# sensor_board_6_1_0.net
KiCad netlist of a schematic drawn in EAGLE
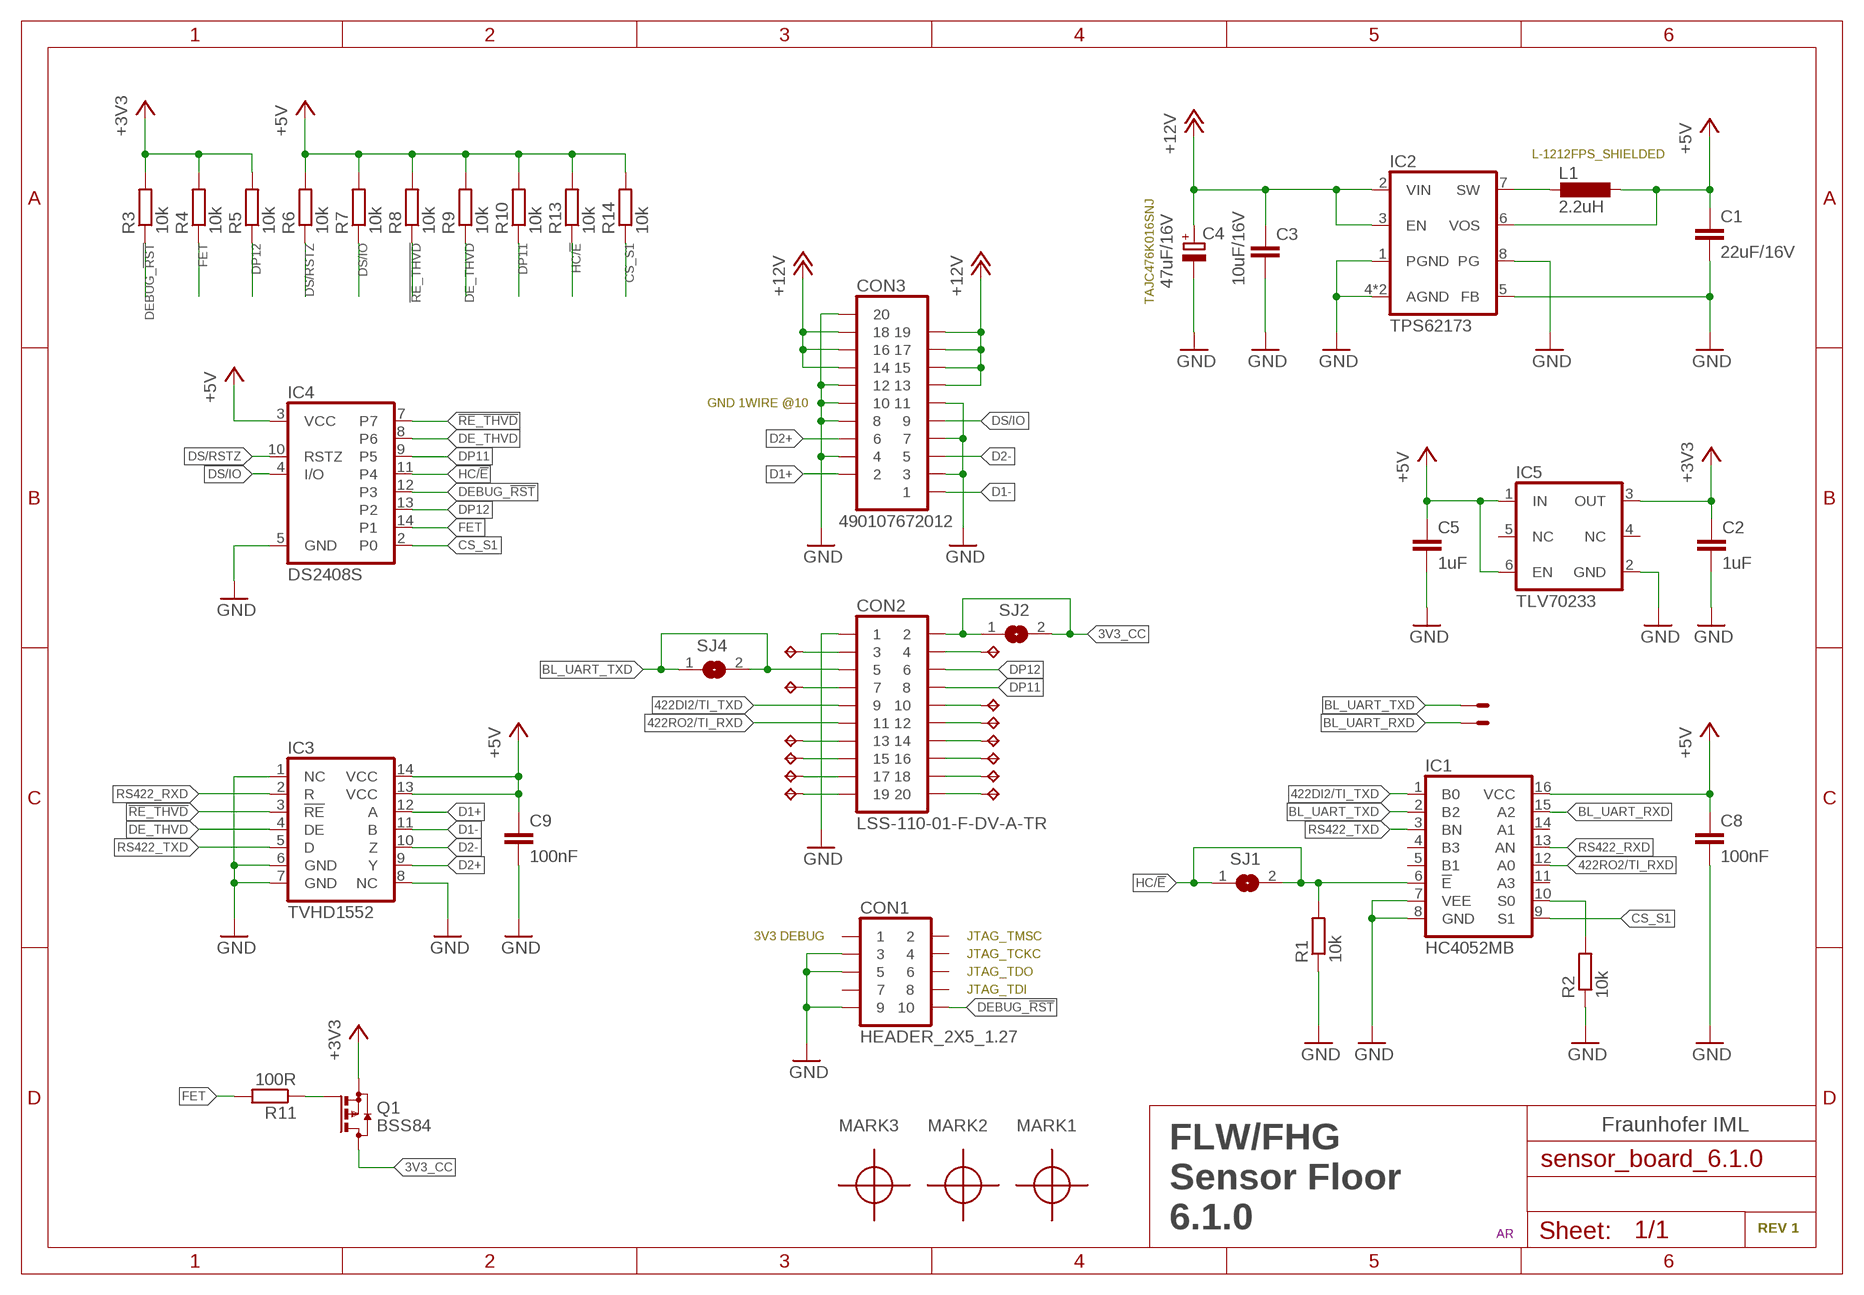
[diagram p0: schematic, sheet 1]

(export (version "E")
  (design (tool "Eeschema 10.0.6"))
  (components
    (comp (ref "C1")
      (value "22uF/16V")
      (footprint "eagle-import:C0805K")
      (libsource (lib "eagle-import") (part "C-EUC0805K"))
    )
    (comp (ref "C2")
      (value "1uF")
      (footprint "eagle-import:C0603")
      (libsource (lib "eagle-import") (part "C0603"))
    )
    (comp (ref "C3")
      (value "10uF/16V")
      (footprint "eagle-import:C0805K")
      (libsource (lib "eagle-import") (part "C-EUC0805K"))
    )
    (comp (ref "C4")
      (value "47uF/16V")
      (footprint "eagle-import:C_6032-28R")
      (libsource (lib "eagle-import") (part "CPOL-EUC/6032-28R"))
    )
    (comp (ref "C5")
      (value "1uF")
      (footprint "eagle-import:C0603")
      (libsource (lib "eagle-import") (part "C0603"))
    )
    (comp (ref "C8")
      (value "100nF")
      (footprint "eagle-import:C0402")
      (libsource (lib "eagle-import") (part "C0402"))
    )
    (comp (ref "C9")
      (value "100nF")
      (footprint "eagle-import:C0402")
      (libsource (lib "eagle-import") (part "C0402"))
    )
    (comp (ref "CON1")
      (value "HEADER_2X5_1.27")
      (footprint "eagle-import:HEADER_2X5_1.27")
      (libsource (lib "eagle-import") (part "HEADER_2X5_1.27"))
    )
    (comp (ref "CON2")
      (value "LSS-110-01-F-DV-A-TR")
      (footprint "eagle-import:LSS-110-01-F-DV-A-TR")
      (libsource (lib "eagle-import") (part "LSS-110-01-F-DV-A-TR"))
    )
    (comp (ref "CON3")
      (value "490107672012")
      (footprint "eagle-import:490107672012")
      (libsource (lib "eagle-import") (part "490107672012"))
    )
    (comp (ref "IC1")
      (value "HC4052MB")
      (footprint "eagle-import:SO16")
      (libsource (lib "eagle-import") (part "HC4052MB"))
    )
    (comp (ref "IC2")
      (value "TPS62173")
      (footprint "eagle-import:WSON8")
      (libsource (lib "eagle-import") (part "TPS62173"))
    )
    (comp (ref "IC3")
      (value "TVHD1552")
      (footprint "eagle-import:SO14")
      (libsource (lib "eagle-import") (part "TVHD1552"))
    )
    (comp (ref "IC4")
      (value "DS2408S")
      (footprint "eagle-import:SO16")
      (libsource (lib "eagle-import") (part "DS2408S"))
    )
    (comp (ref "IC5")
      (value "TLV70233")
      (footprint "eagle-import:S-PDSO-N6")
      (libsource (lib "eagle-import") (part "TLV70233"))
    )
    (comp (ref "L1")
      (value "2.2uH")
      (footprint "eagle-import:L-1212FPS_SHIELDED")
      (libsource (lib "eagle-import") (part "L-1212FPS_SHIELDED"))
    )
    (comp (ref "MARK1")
      (value "PASSMARK")
      (footprint "eagle-import:PASSMARK")
      (libsource (lib "eagle-import") (part "PASSMARK"))
    )
    (comp (ref "MARK2")
      (value "PASSMARK")
      (footprint "eagle-import:PASSMARK")
      (libsource (lib "eagle-import") (part "PASSMARK"))
    )
    (comp (ref "MARK3")
      (value "PASSMARK")
      (footprint "eagle-import:PASSMARK")
      (libsource (lib "eagle-import") (part "PASSMARK"))
    )
    (comp (ref "Q1")
      (value "BSS84")
      (footprint "eagle-import:SOT23")
      (libsource (lib "eagle-import") (part "BSS84"))
    )
    (comp (ref "R1")
      (value "10k")
      (footprint "eagle-import:R0402")
      (libsource (lib "eagle-import") (part "R0402"))
    )
    (comp (ref "R2")
      (value "10k")
      (footprint "eagle-import:R0402")
      (libsource (lib "eagle-import") (part "R0402"))
    )
    (comp (ref "R3")
      (value "10k")
      (footprint "eagle-import:R0402")
      (libsource (lib "eagle-import") (part "R0402"))
    )
    (comp (ref "R4")
      (value "10k")
      (footprint "eagle-import:R0402")
      (libsource (lib "eagle-import") (part "R0402"))
    )
    (comp (ref "R5")
      (value "10k")
      (footprint "eagle-import:R0402")
      (libsource (lib "eagle-import") (part "R0402"))
    )
    (comp (ref "R6")
      (value "10k")
      (footprint "eagle-import:R0402")
      (libsource (lib "eagle-import") (part "R0402"))
    )
    (comp (ref "R7")
      (value "10k")
      (footprint "eagle-import:R0402")
      (libsource (lib "eagle-import") (part "R0402"))
    )
    (comp (ref "R8")
      (value "10k")
      (footprint "eagle-import:R0402")
      (libsource (lib "eagle-import") (part "R0402"))
    )
    (comp (ref "R9")
      (value "10k")
      (footprint "eagle-import:R0402")
      (libsource (lib "eagle-import") (part "R0402"))
    )
    (comp (ref "R10")
      (value "10k")
      (footprint "eagle-import:R0402")
      (libsource (lib "eagle-import") (part "R0402"))
    )
    (comp (ref "R11")
      (value "100R")
      (footprint "eagle-import:R0402")
      (libsource (lib "eagle-import") (part "R0402"))
    )
    (comp (ref "R13")
      (value "10k")
      (footprint "eagle-import:R0402")
      (libsource (lib "eagle-import") (part "R0402"))
    )
    (comp (ref "R14")
      (value "10k")
      (footprint "eagle-import:R0402")
      (libsource (lib "eagle-import") (part "R0402"))
    )
    (comp (ref "SJ1")
      (value "SJT")
      (footprint "eagle-import:SJT")
      (libsource (lib "eagle-import") (part "SJT"))
    )
    (comp (ref "SJ2")
      (value "SJT")
      (footprint "eagle-import:SJT")
      (libsource (lib "eagle-import") (part "SJT"))
    )
    (comp (ref "SJ4")
      (value "SJT")
      (footprint "eagle-import:SJT")
      (libsource (lib "eagle-import") (part "SJT"))
    )
    (comp (ref "TP1")
      (value "TP/SP-1.5X1.0")
      (footprint "eagle-import:SOLDERPAD_1.5X1.0")
      (libsource (lib "eagle-import") (part "TP/SP-1.5X1.0"))
    )
    (comp (ref "TP2")
      (value "TPTP08R")
      (footprint "eagle-import:TP08R")
      (libsource (lib "eagle-import") (part "TPTP08R"))
    )
    (comp (ref "TP3")
      (value "TPTP08R")
      (footprint "eagle-import:TP08R")
      (libsource (lib "eagle-import") (part "TPTP08R"))
    )
    (comp (ref "TP4")
      (value "TP/SP-1.5X1.0")
      (footprint "eagle-import:SOLDERPAD_1.5X1.0")
      (libsource (lib "eagle-import") (part "TP/SP-1.5X1.0"))
    )
    (comp (ref "TP5")
      (value "TPTP08R")
      (footprint "eagle-import:TP08R")
      (libsource (lib "eagle-import") (part "TPTP08R"))
    )
    (comp (ref "TP6")
      (value "TPTP08R")
      (footprint "eagle-import:TP08R")
      (libsource (lib "eagle-import") (part "TPTP08R"))
    )
    (comp (ref "TP7")
      (value "TPTP08R")
      (footprint "eagle-import:TP08R")
      (libsource (lib "eagle-import") (part "TPTP08R"))
    )
    (comp (ref "TP8")
      (value "TPTP08R")
      (footprint "eagle-import:TP08R")
      (libsource (lib "eagle-import") (part "TPTP08R"))
    )
    (comp (ref "TP9")
      (value "TPTP08R")
      (footprint "eagle-import:TP08R")
      (libsource (lib "eagle-import") (part "TPTP08R"))
    )
    (comp (ref "TP10")
      (value "TPTP08R")
      (footprint "eagle-import:TP08R")
      (libsource (lib "eagle-import") (part "TPTP08R"))
    )
    (comp (ref "TP11")
      (value "TPTP08R")
      (footprint "eagle-import:TP08R")
      (libsource (lib "eagle-import") (part "TPTP08R"))
    )
    (comp (ref "TP12")
      (value "TPTP08R")
      (footprint "eagle-import:TP08R")
      (libsource (lib "eagle-import") (part "TPTP08R"))
    )
    (comp (ref "TP13")
      (value "TPTP08R")
      (footprint "eagle-import:TP08R")
      (libsource (lib "eagle-import") (part "TPTP08R"))
    )
    (comp (ref "TP14")
      (value "TPTP08R")
      (footprint "eagle-import:TP08R")
      (libsource (lib "eagle-import") (part "TPTP08R"))
    )
    (comp (ref "TP15")
      (value "TPTP08R")
      (footprint "eagle-import:TP08R")
      (libsource (lib "eagle-import") (part "TPTP08R"))
    )
  )
  (nets
    (net (code "1") (name "+3V3") (class "Default")
      (node (ref "C2") (pin "1") (pinfunction "1_1") (pintype "passive"))
      (node (ref "IC5") (pin "3") (pinfunction "OUT_3") (pintype "power_in"))
      (node (ref "Q1") (pin "2") (pinfunction "S_2") (pintype "passive"))
      (node (ref "R3") (pin "P$2") (pinfunction "2_P$2") (pintype "passive"))
      (node (ref "R4") (pin "P$2") (pinfunction "2_P$2") (pintype "passive"))
      (node (ref "R5") (pin "P$2") (pinfunction "2_P$2") (pintype "passive"))
    )
    (net (code "2") (name "+5V") (class "Default")
      (node (ref "C1") (pin "1") (pinfunction "1_1") (pintype "passive"))
      (node (ref "C5") (pin "1") (pinfunction "1_1") (pintype "passive"))
      (node (ref "C8") (pin "P$1") (pinfunction "1_P$1") (pintype "passive"))
      (node (ref "C9") (pin "P$1") (pinfunction "1_P$1") (pintype "passive"))
      (node (ref "IC1") (pin "16") (pinfunction "VCC_16") (pintype "bidirectional"))
      (node (ref "IC2") (pin "6") (pinfunction "VOS_6") (pintype "bidirectional"))
      (node (ref "IC3") (pin "13") (pinfunction "VCC_13") (pintype "bidirectional"))
      (node (ref "IC3") (pin "14") (pinfunction "VCC_14") (pintype "bidirectional"))
      (node (ref "IC4") (pin "3") (pinfunction "VCC_3") (pintype "power_in"))
      (node (ref "IC5") (pin "1") (pinfunction "IN_1") (pintype "power_in"))
      (node (ref "IC5") (pin "6") (pinfunction "EN_6") (pintype "input"))
      (node (ref "L1") (pin "1") (pinfunction "1_1") (pintype "passive"))
      (node (ref "R10") (pin "P$2") (pinfunction "2_P$2") (pintype "passive"))
      (node (ref "R13") (pin "P$2") (pinfunction "2_P$2") (pintype "passive"))
      (node (ref "R14") (pin "P$2") (pinfunction "2_P$2") (pintype "passive"))
      (node (ref "R6") (pin "P$2") (pinfunction "2_P$2") (pintype "passive"))
      (node (ref "R7") (pin "P$2") (pinfunction "2_P$2") (pintype "passive"))
      (node (ref "R8") (pin "P$2") (pinfunction "2_P$2") (pintype "passive"))
      (node (ref "R9") (pin "P$2") (pinfunction "2_P$2") (pintype "passive"))
    )
    (net (code "3") (name "+12V") (class "Default")
      (node (ref "C3") (pin "1") (pinfunction "1_1") (pintype "passive"))
      (node (ref "C4") (pin "+") (pinfunction "+_+") (pintype "passive"))
      (node (ref "CON3") (pin "13") (pinfunction "13_13") (pintype "passive"))
      (node (ref "CON3") (pin "14") (pinfunction "14_14") (pintype "passive"))
      (node (ref "CON3") (pin "15") (pinfunction "15_15") (pintype "passive"))
      (node (ref "CON3") (pin "16") (pinfunction "16_16") (pintype "passive"))
      (node (ref "CON3") (pin "17") (pinfunction "17_17") (pintype "passive"))
      (node (ref "CON3") (pin "18") (pinfunction "18_18") (pintype "passive"))
      (node (ref "CON3") (pin "19") (pinfunction "19_19") (pintype "passive"))
      (node (ref "IC2") (pin "2") (pinfunction "VIN_2") (pintype "bidirectional"))
      (node (ref "IC2") (pin "3") (pinfunction "EN_3") (pintype "bidirectional"))
    )
    (net (code "4") (name "/DEBUG_~{RST}") (class "Default")
      (node (ref "CON1") (pin "P$10") (pinfunction "10_P$10") (pintype "bidirectional"))
      (node (ref "IC4") (pin "12") (pinfunction "P3_12") (pintype "open_collector"))
      (node (ref "R3") (pin "P$1") (pinfunction "1_P$1") (pintype "passive"))
    )
    (net (code "5") (name "/HC{slash}~{E}") (class "Default")
      (node (ref "IC1") (pin "6") (pinfunction "~{E}_6") (pintype "bidirectional"))
      (node (ref "IC4") (pin "11") (pinfunction "P4_11") (pintype "open_collector"))
      (node (ref "R1") (pin "P$2") (pinfunction "2_P$2") (pintype "passive"))
      (node (ref "R13") (pin "P$1") (pinfunction "1_P$1") (pintype "passive"))
      (node (ref "SJ1") (pin "1") (pinfunction "1_1") (pintype "passive"))
      (node (ref "SJ1") (pin "2") (pinfunction "2_2") (pintype "passive"))
    )
    (net (code "6") (name "/~{RE_THVD}") (class "Default")
      (node (ref "IC3") (pin "3") (pinfunction "~{RE}_3") (pintype "bidirectional"))
      (node (ref "IC4") (pin "7") (pinfunction "P7_7") (pintype "open_collector"))
      (node (ref "R8") (pin "P$1") (pinfunction "1_P$1") (pintype "passive"))
    )
    (net (code "7") (name "3V3_CC") (class "Default")
      (node (ref "CON2") (pin "P2") (pinfunction "2_P2") (pintype "bidirectional"))
      (node (ref "Q1") (pin "3") (pinfunction "D_3") (pintype "passive"))
      (node (ref "SJ2") (pin "1") (pinfunction "1_1") (pintype "passive"))
      (node (ref "SJ2") (pin "2") (pinfunction "2_2") (pintype "passive"))
    )
    (net (code "8") (name "422DI2{slash}TI_TXD") (class "Default")
      (node (ref "CON2") (pin "P9") (pinfunction "9_P9") (pintype "bidirectional"))
      (node (ref "IC1") (pin "1") (pinfunction "B0_1") (pintype "bidirectional"))
    )
    (net (code "9") (name "422RO2{slash}TI_RXD") (class "Default")
      (node (ref "CON2") (pin "P11") (pinfunction "11_P11") (pintype "bidirectional"))
      (node (ref "IC1") (pin "12") (pinfunction "A0_12") (pintype "bidirectional"))
    )
    (net (code "10") (name "BL_UART_RXD") (class "Default")
      (node (ref "IC1") (pin "15") (pinfunction "A2_15") (pintype "bidirectional"))
      (node (ref "TP4") (pin "1") (pinfunction "S_1") (pintype "passive"))
    )
    (net (code "11") (name "BL_UART_TXD") (class "Default")
      (node (ref "CON2") (pin "P5") (pinfunction "5_P5") (pintype "bidirectional"))
      (node (ref "IC1") (pin "2") (pinfunction "B2_2") (pintype "bidirectional"))
      (node (ref "SJ4") (pin "1") (pinfunction "1_1") (pintype "passive"))
      (node (ref "SJ4") (pin "2") (pinfunction "2_2") (pintype "passive"))
      (node (ref "TP1") (pin "1") (pinfunction "S_1") (pintype "passive"))
    )
    (net (code "12") (name "CS_S1") (class "Default")
      (node (ref "IC1") (pin "9") (pinfunction "S1_9") (pintype "bidirectional"))
      (node (ref "IC4") (pin "2") (pinfunction "P0_2") (pintype "open_collector"))
      (node (ref "R14") (pin "P$1") (pinfunction "1_P$1") (pintype "passive"))
    )
    (net (code "13") (name "D1+") (class "Default")
      (node (ref "CON3") (pin "2") (pinfunction "2_2") (pintype "passive"))
      (node (ref "IC3") (pin "12") (pinfunction "A_12") (pintype "bidirectional"))
    )
    (net (code "14") (name "D1-") (class "Default")
      (node (ref "CON3") (pin "1") (pinfunction "1_1") (pintype "passive"))
      (node (ref "IC3") (pin "11") (pinfunction "B_11") (pintype "bidirectional"))
    )
    (net (code "15") (name "D2+") (class "Default")
      (node (ref "CON3") (pin "6") (pinfunction "6_6") (pintype "passive"))
      (node (ref "IC3") (pin "9") (pinfunction "Y_9") (pintype "bidirectional"))
    )
    (net (code "16") (name "D2-") (class "Default")
      (node (ref "CON3") (pin "5") (pinfunction "5_5") (pintype "passive"))
      (node (ref "IC3") (pin "10") (pinfunction "Z_10") (pintype "bidirectional"))
    )
    (net (code "17") (name "DE_THVD") (class "Default")
      (node (ref "IC3") (pin "4") (pinfunction "DE_4") (pintype "bidirectional"))
      (node (ref "IC4") (pin "8") (pinfunction "P6_8") (pintype "open_collector"))
      (node (ref "R9") (pin "P$1") (pinfunction "1_P$1") (pintype "passive"))
    )
    (net (code "18") (name "DP11") (class "Default")
      (node (ref "CON2") (pin "P8") (pinfunction "8_P8") (pintype "bidirectional"))
      (node (ref "IC4") (pin "9") (pinfunction "P5_9") (pintype "open_collector"))
      (node (ref "R10") (pin "P$1") (pinfunction "1_P$1") (pintype "passive"))
    )
    (net (code "19") (name "DP12") (class "Default")
      (node (ref "CON2") (pin "P6") (pinfunction "6_P6") (pintype "bidirectional"))
      (node (ref "IC4") (pin "13") (pinfunction "P2_13") (pintype "open_collector"))
      (node (ref "R5") (pin "P$1") (pinfunction "1_P$1") (pintype "passive"))
    )
    (net (code "20") (name "DS{slash}IO") (class "Default")
      (node (ref "CON3") (pin "9") (pinfunction "9_9") (pintype "passive"))
      (node (ref "IC4") (pin "4") (pinfunction "I/O_4") (pintype "open_collector"))
      (node (ref "R7") (pin "P$1") (pinfunction "1_P$1") (pintype "passive"))
    )
    (net (code "21") (name "DS{slash}RSTZ") (class "Default")
      (node (ref "IC4") (pin "10") (pinfunction "RSTZ_10") (pintype "open_collector"))
      (node (ref "R6") (pin "P$1") (pinfunction "1_P$1") (pintype "passive"))
    )
    (net (code "22") (name "FET") (class "Default")
      (node (ref "IC4") (pin "14") (pinfunction "P1_14") (pintype "open_collector"))
      (node (ref "R11") (pin "P$2") (pinfunction "2_P$2") (pintype "passive"))
      (node (ref "R4") (pin "P$1") (pinfunction "1_P$1") (pintype "passive"))
    )
    (net (code "23") (name "GND") (class "Default")
      (node (ref "C1") (pin "2") (pinfunction "2_2") (pintype "passive"))
      (node (ref "C2") (pin "2") (pinfunction "2_2") (pintype "passive"))
      (node (ref "C3") (pin "2") (pinfunction "2_2") (pintype "passive"))
      (node (ref "C4") (pin "-") (pinfunction "-_-") (pintype "passive"))
      (node (ref "C5") (pin "2") (pinfunction "2_2") (pintype "passive"))
      (node (ref "C8") (pin "P$2") (pinfunction "2_P$2") (pintype "passive"))
      (node (ref "C9") (pin "P$2") (pinfunction "2_P$2") (pintype "passive"))
      (node (ref "CON1") (pin "P$3") (pinfunction "3_P$3") (pintype "bidirectional"))
      (node (ref "CON1") (pin "P$5") (pinfunction "5_P$5") (pintype "bidirectional"))
      (node (ref "CON1") (pin "P$9") (pinfunction "9_P$9") (pintype "bidirectional"))
      (node (ref "CON2") (pin "P1") (pinfunction "1_P1") (pintype "bidirectional"))
      (node (ref "CON3") (pin "10") (pinfunction "10_10") (pintype "passive"))
      (node (ref "CON3") (pin "11") (pinfunction "11_11") (pintype "passive"))
      (node (ref "CON3") (pin "12") (pinfunction "12_12") (pintype "passive"))
      (node (ref "CON3") (pin "20") (pinfunction "20_20") (pintype "passive"))
      (node (ref "CON3") (pin "3") (pinfunction "3_3") (pintype "passive"))
      (node (ref "CON3") (pin "4") (pinfunction "4_4") (pintype "passive"))
      (node (ref "CON3") (pin "7") (pinfunction "7_7") (pintype "passive"))
      (node (ref "CON3") (pin "8") (pinfunction "8_8") (pintype "passive"))
      (node (ref "IC1") (pin "7") (pinfunction "VEE_7") (pintype "bidirectional"))
      (node (ref "IC1") (pin "8") (pinfunction "GND_8") (pintype "bidirectional"))
      (node (ref "IC2") (pin "1") (pinfunction "PGND_1") (pintype "bidirectional"))
      (node (ref "IC2") (pin "4") (pinfunction "AGND_4") (pintype "bidirectional"))
      (node (ref "IC2") (pin "5") (pinfunction "FB_5") (pintype "bidirectional"))
      (node (ref "IC2") (pin "8") (pinfunction "PG_8") (pintype "bidirectional"))
      (node (ref "IC2") (pin "EXP") (pinfunction "AGND_EXP") (pintype "bidirectional"))
      (node (ref "IC3") (pin "1") (pinfunction "NC_1") (pintype "bidirectional"))
      (node (ref "IC3") (pin "6") (pinfunction "GND_6") (pintype "bidirectional"))
      (node (ref "IC3") (pin "7") (pinfunction "GND_7") (pintype "bidirectional"))
      (node (ref "IC3") (pin "8") (pinfunction "NC_8") (pintype "bidirectional"))
      (node (ref "IC4") (pin "5") (pinfunction "GND_5") (pintype "power_in"))
      (node (ref "IC5") (pin "2") (pinfunction "GND_2") (pintype "power_in"))
      (node (ref "R1") (pin "P$1") (pinfunction "1_P$1") (pintype "passive"))
      (node (ref "R2") (pin "P$1") (pinfunction "1_P$1") (pintype "passive"))
    )
    (net (code "24") (name "Net-(CON2-3)") (class "Default")
      (node (ref "CON2") (pin "P3") (pinfunction "3_P3") (pintype "bidirectional"))
      (node (ref "TP15") (pin "TP") (pinfunction "TP_TP") (pintype "input"))
    )
    (net (code "25") (name "Net-(CON2-4)") (class "Default")
      (node (ref "CON2") (pin "P4") (pinfunction "4_P4") (pintype "bidirectional"))
      (node (ref "TP14") (pin "TP") (pinfunction "TP_TP") (pintype "input"))
    )
    (net (code "26") (name "Net-(CON2-7)") (class "Default")
      (node (ref "CON2") (pin "P7") (pinfunction "7_P7") (pintype "bidirectional"))
      (node (ref "TP13") (pin "TP") (pinfunction "TP_TP") (pintype "input"))
    )
    (net (code "27") (name "Net-(CON2-10)") (class "Default")
      (node (ref "CON2") (pin "P10") (pinfunction "10_P10") (pintype "bidirectional"))
      (node (ref "TP3") (pin "TP") (pinfunction "TP_TP") (pintype "input"))
    )
    (net (code "28") (name "Net-(CON2-12)") (class "Default")
      (node (ref "CON2") (pin "P12") (pinfunction "12_P12") (pintype "bidirectional"))
      (node (ref "TP2") (pin "TP") (pinfunction "TP_TP") (pintype "input"))
    )
    (net (code "29") (name "Net-(CON2-13)") (class "Default")
      (node (ref "CON2") (pin "P13") (pinfunction "13_P13") (pintype "bidirectional"))
      (node (ref "TP12") (pin "TP") (pinfunction "TP_TP") (pintype "input"))
    )
    (net (code "30") (name "Net-(CON2-14)") (class "Default")
      (node (ref "CON2") (pin "P14") (pinfunction "14_P14") (pintype "bidirectional"))
      (node (ref "TP5") (pin "TP") (pinfunction "TP_TP") (pintype "input"))
    )
    (net (code "31") (name "Net-(CON2-15)") (class "Default")
      (node (ref "CON2") (pin "P15") (pinfunction "15_P15") (pintype "bidirectional"))
      (node (ref "TP11") (pin "TP") (pinfunction "TP_TP") (pintype "input"))
    )
    (net (code "32") (name "Net-(CON2-16)") (class "Default")
      (node (ref "CON2") (pin "P16") (pinfunction "16_P16") (pintype "bidirectional"))
      (node (ref "TP6") (pin "TP") (pinfunction "TP_TP") (pintype "input"))
    )
    (net (code "33") (name "Net-(CON2-17)") (class "Default")
      (node (ref "CON2") (pin "P17") (pinfunction "17_P17") (pintype "bidirectional"))
      (node (ref "TP10") (pin "TP") (pinfunction "TP_TP") (pintype "input"))
    )
    (net (code "34") (name "Net-(CON2-18)") (class "Default")
      (node (ref "CON2") (pin "P18") (pinfunction "18_P18") (pintype "bidirectional"))
      (node (ref "TP7") (pin "TP") (pinfunction "TP_TP") (pintype "input"))
    )
    (net (code "35") (name "Net-(CON2-19)") (class "Default")
      (node (ref "CON2") (pin "P19") (pinfunction "19_P19") (pintype "bidirectional"))
      (node (ref "TP9") (pin "TP") (pinfunction "TP_TP") (pintype "input"))
    )
    (net (code "36") (name "Net-(CON2-20)") (class "Default")
      (node (ref "CON2") (pin "P20") (pinfunction "20_P20") (pintype "bidirectional"))
      (node (ref "TP8") (pin "TP") (pinfunction "TP_TP") (pintype "input"))
    )
    (net (code "37") (name "Net-(IC1-S0)") (class "Default")
      (node (ref "IC1") (pin "10") (pinfunction "S0_10") (pintype "bidirectional"))
      (node (ref "R2") (pin "P$2") (pinfunction "2_P$2") (pintype "passive"))
    )
    (net (code "38") (name "Net-(IC2-SW)") (class "Default")
      (node (ref "IC2") (pin "7") (pinfunction "SW_7") (pintype "bidirectional"))
      (node (ref "L1") (pin "2") (pinfunction "2_2") (pintype "passive"))
    )
    (net (code "39") (name "Net-(Q1-G)") (class "Default")
      (node (ref "Q1") (pin "1") (pinfunction "G_1") (pintype "passive"))
      (node (ref "R11") (pin "P$1") (pinfunction "1_P$1") (pintype "passive"))
    )
    (net (code "40") (name "RS422_RXD") (class "Default")
      (node (ref "IC1") (pin "13") (pinfunction "AN_13") (pintype "bidirectional"))
      (node (ref "IC3") (pin "2") (pinfunction "R_2") (pintype "bidirectional"))
    )
    (net (code "41") (name "RS422_TXD") (class "Default")
      (node (ref "IC1") (pin "3") (pinfunction "BN_3") (pintype "bidirectional"))
      (node (ref "IC3") (pin "5") (pinfunction "D_5") (pintype "bidirectional"))
    )
    (net (code "42") (name "unconnected-(CON1-1-PadP$1)") (class "Default")
      (node (ref "CON1") (pin "P$1") (pinfunction "1_P$1") (pintype "bidirectional"))
    )
    (net (code "43") (name "unconnected-(CON1-2-PadP$2)") (class "Default")
      (node (ref "CON1") (pin "P$2") (pinfunction "2_P$2") (pintype "bidirectional"))
    )
    (net (code "44") (name "unconnected-(CON1-4-PadP$4)") (class "Default")
      (node (ref "CON1") (pin "P$4") (pinfunction "4_P$4") (pintype "bidirectional"))
    )
    (net (code "45") (name "unconnected-(CON1-6-PadP$6)") (class "Default")
      (node (ref "CON1") (pin "P$6") (pinfunction "6_P$6") (pintype "bidirectional"))
    )
    (net (code "46") (name "unconnected-(CON1-7-PadP$7)") (class "Default")
      (node (ref "CON1") (pin "P$7") (pinfunction "7_P$7") (pintype "bidirectional"))
    )
    (net (code "47") (name "unconnected-(CON1-8-PadP$8)") (class "Default")
      (node (ref "CON1") (pin "P$8") (pinfunction "8_P$8") (pintype "bidirectional"))
    )
    (net (code "48") (name "unconnected-(IC1-A1-Pad14)") (class "Default")
      (node (ref "IC1") (pin "14") (pinfunction "A1_14") (pintype "bidirectional"))
    )
    (net (code "49") (name "unconnected-(IC1-A3-Pad11)") (class "Default")
      (node (ref "IC1") (pin "11") (pinfunction "A3_11") (pintype "bidirectional"))
    )
    (net (code "50") (name "unconnected-(IC1-B1-Pad5)") (class "Default")
      (node (ref "IC1") (pin "5") (pinfunction "B1_5") (pintype "bidirectional"))
    )
    (net (code "51") (name "unconnected-(IC1-B3-Pad4)") (class "Default")
      (node (ref "IC1") (pin "4") (pinfunction "B3_4") (pintype "bidirectional"))
    )
    (net (code "52") (name "unconnected-(IC5-NC-Pad4)") (class "Default")
      (node (ref "IC5") (pin "4") (pinfunction "NC_4") (pintype "no_connect"))
    )
    (net (code "53") (name "unconnected-(IC5-NC-Pad5)") (class "Default")
      (node (ref "IC5") (pin "5") (pinfunction "NC_5") (pintype "no_connect"))
    )
  )
)
